# OCXO.net
KiCad netlist of a schematic drawn in Altium Designer
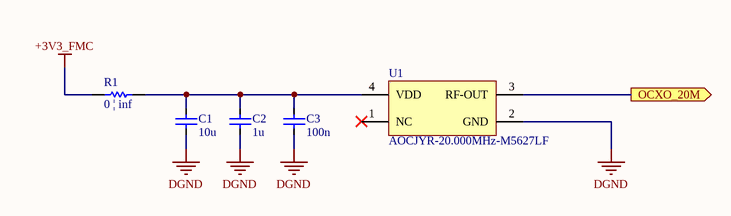
[diagram p0: OCXO.SchDoc]

(export (version "E")
  (design (tool "Eeschema 10.0.6"))
  (components
    (comp (ref "C1") (value "10u") (footprint "CAP_0603") (libsource (lib "IIS-Lib_TW") (part "Cap")))
    (comp (ref "C2") (value "1u") (footprint "CAP_0402") (libsource (lib "IIS-Lib_TW") (part "Cap")))
    (comp (ref "C3") (value "100n") (footprint "CAP_0402") (libsource (lib "IIS-Lib_TW") (part "Cap")))
    (comp (ref "R1") (value "0 ¦ inf") (footprint "RES_0402") (libsource (lib "IIS-Lib_TW") (part "Res")))
    (comp (ref "U1")
      (value "AOCJYR-20.000MHz-M5627LF")
      (footprint "AOCJYR20000MHZM5627LFT")
      (libsource (lib "IIS-Lib_TW") (part "AOCJYR-20.000MHz-M5627LF"))
    )
  )
  (nets
    (net (code "1") (name "+3V3_FMC") (class "Default")
      (node (ref "R1") (pin "2") (pinfunction "2_2") (pintype "passive"))
    )
    (net (code "2") (name "/OCXO_20M") (class "Default")
      (node (ref "U1") (pin "3") (pinfunction "RF-OUT_3") (pintype "passive"))
    )
    (net (code "3") (name "DGND") (class "Default")
      (node (ref "C1") (pin "2") (pinfunction "2_2") (pintype "passive"))
      (node (ref "C2") (pin "2") (pinfunction "2_2") (pintype "passive"))
      (node (ref "C3") (pin "2") (pinfunction "2_2") (pintype "passive"))
      (node (ref "U1") (pin "2") (pinfunction "GND_2") (pintype "passive"))
    )
    (net (code "4") (name "Net-(U1-VDD)") (class "Default")
      (node (ref "C1") (pin "1") (pinfunction "1_1") (pintype "passive"))
      (node (ref "C2") (pin "1") (pinfunction "1_1") (pintype "passive"))
      (node (ref "C3") (pin "1") (pinfunction "1_1") (pintype "passive"))
      (node (ref "R1") (pin "1") (pinfunction "1_1") (pintype "passive"))
      (node (ref "U1") (pin "4") (pinfunction "VDD_4") (pintype "passive"))
    )
    (net (code "5") (name "unconnected-(U1-NC-Pad1)") (class "Default")
      (node (ref "U1") (pin "1") (pinfunction "NC_1") (pintype "passive+no_connect"))
    )
  )
)
